# NovaSMTPracticeVX.net
KiCad netlist of a schematic drawn in EAGLE
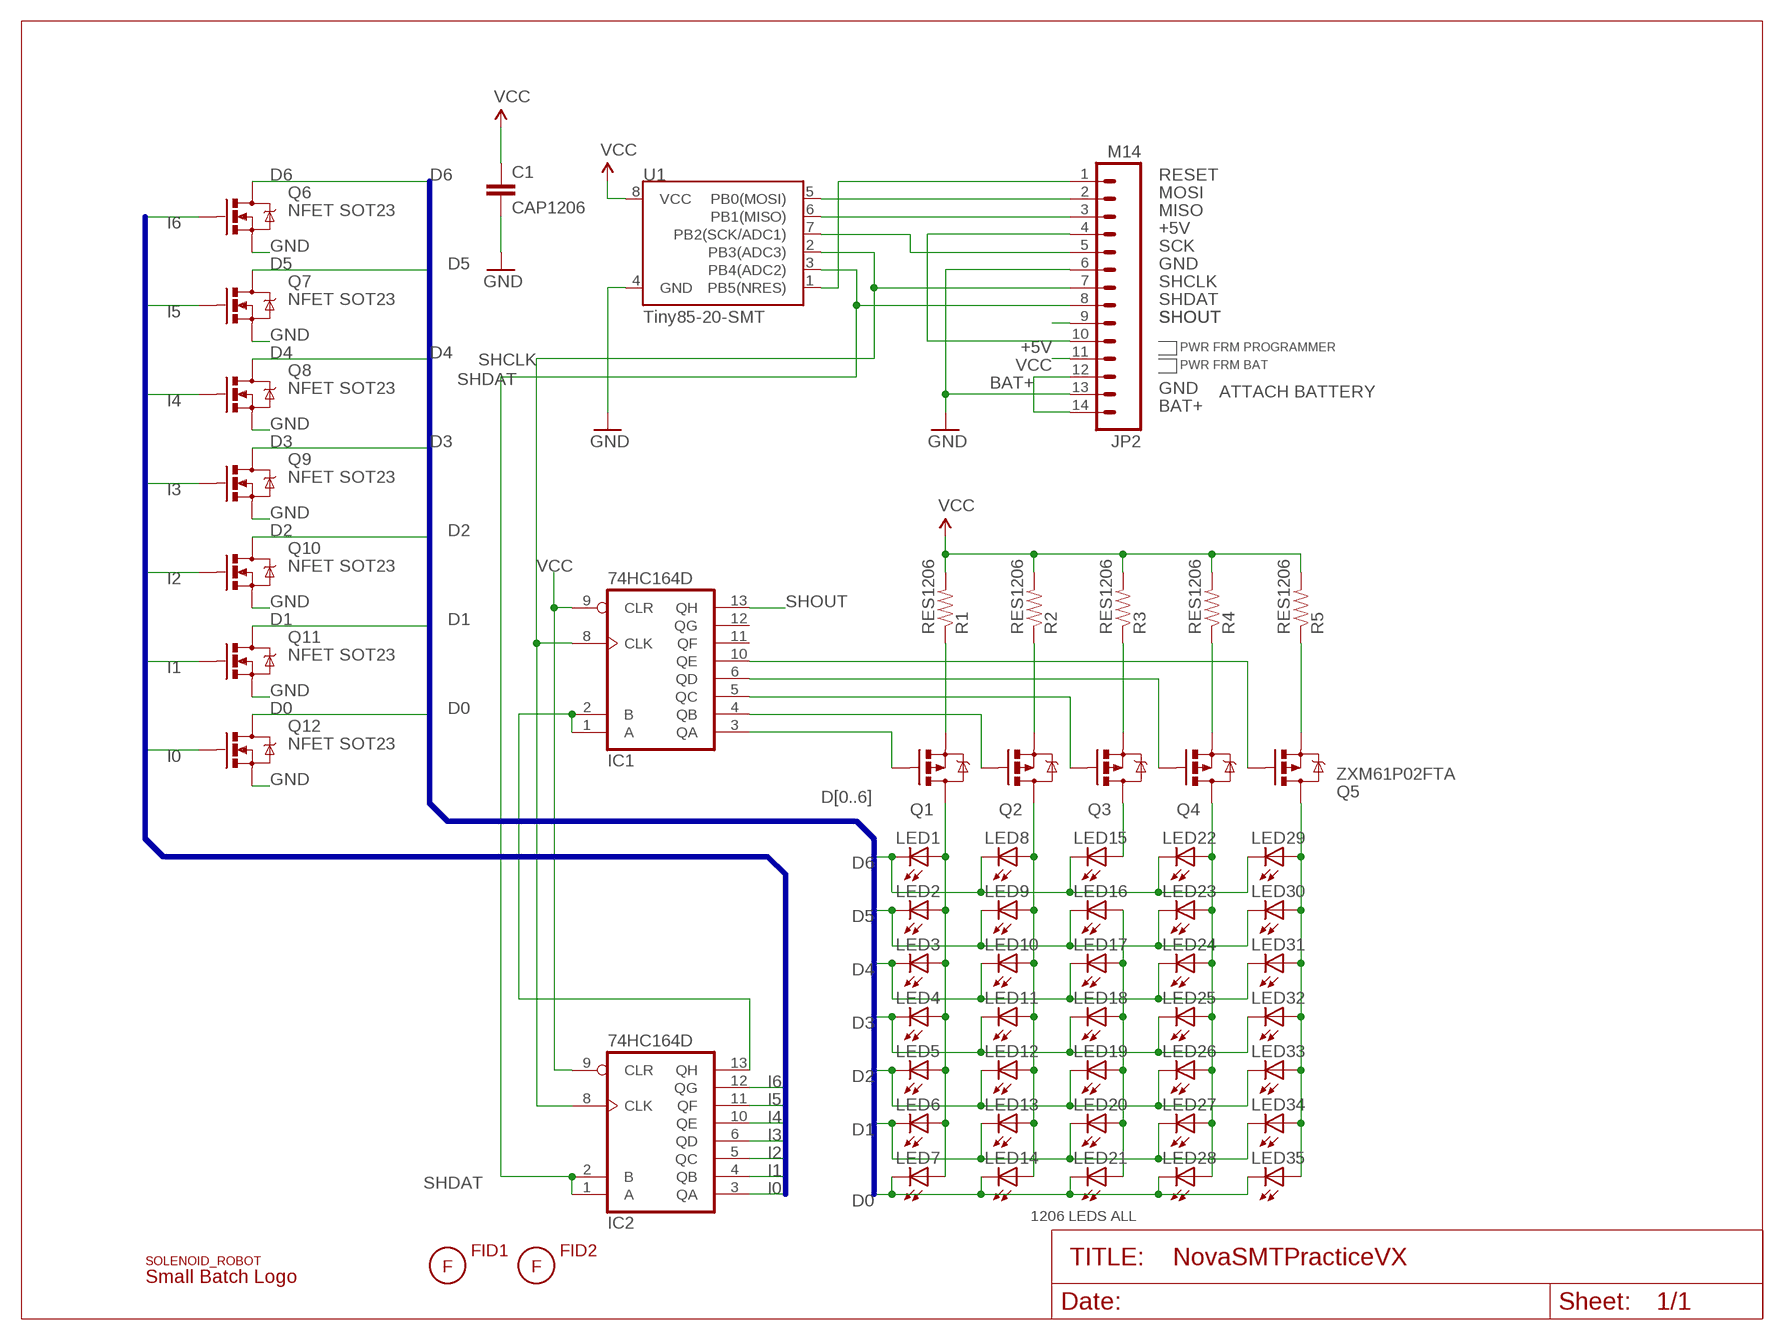
[diagram p0: schematic, sheet 1]

(export (version "E")
  (design (tool "Eeschema 10.0.6"))
  (components
    (comp (ref "C1")
      (value "CAP1206")
      (footprint "eagle-import:1206")
      (libsource (lib "eagle-import") (part "CAP1206"))
    )
    (comp (ref "FID1")
      (value "FIDUCIAL")
      (footprint "eagle-import:FID05MM")
      (libsource (lib "eagle-import") (part "FIDUCIAL"))
    )
    (comp (ref "FID2")
      (value "FIDUCIAL")
      (footprint "eagle-import:FID05MM")
      (libsource (lib "eagle-import") (part "FIDUCIAL"))
    )
    (comp (ref "IC1")
      (value "74HC164D")
      (footprint "eagle-import:SO14")
      (libsource (lib "eagle-import") (part "74164DHC"))
    )
    (comp (ref "IC2")
      (value "74HC164D")
      (footprint "eagle-import:SO14")
      (libsource (lib "eagle-import") (part "74164DHC"))
    )
    (comp (ref "JP2")
      (value "M14")
      (footprint "eagle-import:1X14_SMTPADS")
      (libsource (lib "eagle-import") (part "M14"))
    )
    (comp (ref "LED1")
      (value "LED1206")
      (footprint "eagle-import:LED-1206")
      (libsource (lib "eagle-import") (part "LED1206"))
    )
    (comp (ref "LED2")
      (value "LED1206")
      (footprint "eagle-import:LED-1206")
      (libsource (lib "eagle-import") (part "LED1206"))
    )
    (comp (ref "LED3")
      (value "LED1206")
      (footprint "eagle-import:LED-1206")
      (libsource (lib "eagle-import") (part "LED1206"))
    )
    (comp (ref "LED4")
      (value "LED1206")
      (footprint "eagle-import:LED-1206")
      (libsource (lib "eagle-import") (part "LED1206"))
    )
    (comp (ref "LED5")
      (value "LED1206")
      (footprint "eagle-import:LED-1206")
      (libsource (lib "eagle-import") (part "LED1206"))
    )
    (comp (ref "LED6")
      (value "LED1206")
      (footprint "eagle-import:LED-1206")
      (libsource (lib "eagle-import") (part "LED1206"))
    )
    (comp (ref "LED7")
      (value "LED1206")
      (footprint "eagle-import:LED-1206")
      (libsource (lib "eagle-import") (part "LED1206"))
    )
    (comp (ref "LED8")
      (value "LED1206")
      (footprint "eagle-import:LED-1206")
      (libsource (lib "eagle-import") (part "LED1206"))
    )
    (comp (ref "LED9")
      (value "LED1206")
      (footprint "eagle-import:LED-1206")
      (libsource (lib "eagle-import") (part "LED1206"))
    )
    (comp (ref "LED10")
      (value "LED1206")
      (footprint "eagle-import:LED-1206")
      (libsource (lib "eagle-import") (part "LED1206"))
    )
    (comp (ref "LED11")
      (value "LED1206")
      (footprint "eagle-import:LED-1206")
      (libsource (lib "eagle-import") (part "LED1206"))
    )
    (comp (ref "LED12")
      (value "LED1206")
      (footprint "eagle-import:LED-1206")
      (libsource (lib "eagle-import") (part "LED1206"))
    )
    (comp (ref "LED13")
      (value "LED1206")
      (footprint "eagle-import:LED-1206")
      (libsource (lib "eagle-import") (part "LED1206"))
    )
    (comp (ref "LED14")
      (value "LED1206")
      (footprint "eagle-import:LED-1206")
      (libsource (lib "eagle-import") (part "LED1206"))
    )
    (comp (ref "LED15")
      (value "LED1206")
      (footprint "eagle-import:LED-1206")
      (libsource (lib "eagle-import") (part "LED1206"))
    )
    (comp (ref "LED16")
      (value "LED1206")
      (footprint "eagle-import:LED-1206")
      (libsource (lib "eagle-import") (part "LED1206"))
    )
    (comp (ref "LED17")
      (value "LED1206")
      (footprint "eagle-import:LED-1206")
      (libsource (lib "eagle-import") (part "LED1206"))
    )
    (comp (ref "LED18")
      (value "LED1206")
      (footprint "eagle-import:LED-1206")
      (libsource (lib "eagle-import") (part "LED1206"))
    )
    (comp (ref "LED19")
      (value "LED1206")
      (footprint "eagle-import:LED-1206")
      (libsource (lib "eagle-import") (part "LED1206"))
    )
    (comp (ref "LED20")
      (value "LED1206")
      (footprint "eagle-import:LED-1206")
      (libsource (lib "eagle-import") (part "LED1206"))
    )
    (comp (ref "LED21")
      (value "LED1206")
      (footprint "eagle-import:LED-1206")
      (libsource (lib "eagle-import") (part "LED1206"))
    )
    (comp (ref "LED22")
      (value "LED1206")
      (footprint "eagle-import:LED-1206")
      (libsource (lib "eagle-import") (part "LED1206"))
    )
    (comp (ref "LED23")
      (value "LED1206")
      (footprint "eagle-import:LED-1206")
      (libsource (lib "eagle-import") (part "LED1206"))
    )
    (comp (ref "LED24")
      (value "LED1206")
      (footprint "eagle-import:LED-1206")
      (libsource (lib "eagle-import") (part "LED1206"))
    )
    (comp (ref "LED25")
      (value "LED1206")
      (footprint "eagle-import:LED-1206")
      (libsource (lib "eagle-import") (part "LED1206"))
    )
    (comp (ref "LED26")
      (value "LED1206")
      (footprint "eagle-import:LED-1206")
      (libsource (lib "eagle-import") (part "LED1206"))
    )
    (comp (ref "LED27")
      (value "LED1206")
      (footprint "eagle-import:LED-1206")
      (libsource (lib "eagle-import") (part "LED1206"))
    )
    (comp (ref "LED28")
      (value "LED1206")
      (footprint "eagle-import:LED-1206")
      (libsource (lib "eagle-import") (part "LED1206"))
    )
    (comp (ref "LED29")
      (value "LED1206")
      (footprint "eagle-import:LED-1206")
      (libsource (lib "eagle-import") (part "LED1206"))
    )
    (comp (ref "LED30")
      (value "LED1206")
      (footprint "eagle-import:LED-1206")
      (libsource (lib "eagle-import") (part "LED1206"))
    )
    (comp (ref "LED31")
      (value "LED1206")
      (footprint "eagle-import:LED-1206")
      (libsource (lib "eagle-import") (part "LED1206"))
    )
    (comp (ref "LED32")
      (value "LED1206")
      (footprint "eagle-import:LED-1206")
      (libsource (lib "eagle-import") (part "LED1206"))
    )
    (comp (ref "LED33")
      (value "LED1206")
      (footprint "eagle-import:LED-1206")
      (libsource (lib "eagle-import") (part "LED1206"))
    )
    (comp (ref "LED34")
      (value "LED1206")
      (footprint "eagle-import:LED-1206")
      (libsource (lib "eagle-import") (part "LED1206"))
    )
    (comp (ref "LED35")
      (value "LED1206")
      (footprint "eagle-import:LED-1206")
      (libsource (lib "eagle-import") (part "LED1206"))
    )
    (comp (ref "Q1")
      (value "MOSFET-PCHANNELSMD")
      (footprint "eagle-import:SOT23-3")
      (libsource (lib "eagle-import") (part "MOSFET-PCHANNELSMD"))
    )
    (comp (ref "Q2")
      (value "MOSFET-PCHANNELSMD")
      (footprint "eagle-import:SOT23-3")
      (libsource (lib "eagle-import") (part "MOSFET-PCHANNELSMD"))
    )
    (comp (ref "Q3")
      (value "MOSFET-PCHANNELSMD")
      (footprint "eagle-import:SOT23-3")
      (libsource (lib "eagle-import") (part "MOSFET-PCHANNELSMD"))
    )
    (comp (ref "Q4")
      (value "MOSFET-PCHANNELSMD")
      (footprint "eagle-import:SOT23-3")
      (libsource (lib "eagle-import") (part "MOSFET-PCHANNELSMD"))
    )
    (comp (ref "Q5")
      (value "ZXM61P02FTA")
      (footprint "eagle-import:SOT23-3")
      (libsource (lib "eagle-import") (part "MOSFET-PCHANNELSMD"))
    )
    (comp (ref "Q6")
      (value "NFET SOT23")
      (footprint "eagle-import:SOT23-3")
      (libsource (lib "eagle-import") (part "MOSFET-NCHANNELSMD"))
    )
    (comp (ref "Q7")
      (value "NFET SOT23")
      (footprint "eagle-import:SOT23-3")
      (libsource (lib "eagle-import") (part "MOSFET-NCHANNELSMD"))
    )
    (comp (ref "Q8")
      (value "NFET SOT23")
      (footprint "eagle-import:SOT23-3")
      (libsource (lib "eagle-import") (part "MOSFET-NCHANNELSMD"))
    )
    (comp (ref "Q9")
      (value "NFET SOT23")
      (footprint "eagle-import:SOT23-3")
      (libsource (lib "eagle-import") (part "MOSFET-NCHANNELSMD"))
    )
    (comp (ref "Q10")
      (value "NFET SOT23")
      (footprint "eagle-import:SOT23-3")
      (libsource (lib "eagle-import") (part "MOSFET-NCHANNELSMD"))
    )
    (comp (ref "Q11")
      (value "NFET SOT23")
      (footprint "eagle-import:SOT23-3")
      (libsource (lib "eagle-import") (part "MOSFET-NCHANNELSMD"))
    )
    (comp (ref "Q12")
      (value "NFET SOT23")
      (footprint "eagle-import:SOT23-3")
      (libsource (lib "eagle-import") (part "MOSFET-NCHANNELSMD"))
    )
    (comp (ref "R1")
      (value "RES1206")
      (footprint "eagle-import:1206")
      (libsource (lib "eagle-import") (part "RES1206"))
    )
    (comp (ref "R2")
      (value "RES1206")
      (footprint "eagle-import:1206")
      (libsource (lib "eagle-import") (part "RES1206"))
    )
    (comp (ref "R3")
      (value "RES1206")
      (footprint "eagle-import:1206")
      (libsource (lib "eagle-import") (part "RES1206"))
    )
    (comp (ref "R4")
      (value "RES1206")
      (footprint "eagle-import:1206")
      (libsource (lib "eagle-import") (part "RES1206"))
    )
    (comp (ref "R5")
      (value "RES1206")
      (footprint "eagle-import:1206")
      (libsource (lib "eagle-import") (part "RES1206"))
    )
    (comp (ref "U$1")
      (value "SOLENOID_ROBOT")
      (footprint "eagle-import:SOLENOID_ROBT_450MIL")
      (libsource (lib "eagle-import") (part "SOLENOID_ROBOT"))
    )
    (comp (ref "U$4")
      (value "SMALLBATCH_LOGO750W")
      (footprint "eagle-import:SMALLBATCH_750W")
      (libsource (lib "eagle-import") (part "SMALLBATCH_LOGO750W"))
    )
    (comp (ref "U1")
      (value "Tiny85-20-SMT")
      (footprint "eagle-import:SO08-EIAJ")
      (libsource (lib "eagle-import") (part "ATTINY45TINY85-20-SMT"))
    )
  )
  (nets
    (net (code "1") (name "/+5V") (class "Default")
      (node (ref "JP2") (pin "10") (pinfunction "10_10") (pintype "passive"))
      (node (ref "JP2") (pin "4") (pinfunction "4_4") (pintype "passive"))
    )
    (net (code "2") (name "/BAT+") (class "Default")
      (node (ref "JP2") (pin "12") (pinfunction "12_12") (pintype "passive"))
      (node (ref "JP2") (pin "14") (pinfunction "14_14") (pintype "passive"))
    )
    (net (code "3") (name "/D0") (class "Default")
      (node (ref "LED14") (pin "C") (pinfunction "C_C") (pintype "passive"))
      (node (ref "LED21") (pin "C") (pinfunction "C_C") (pintype "passive"))
      (node (ref "LED28") (pin "C") (pinfunction "C_C") (pintype "passive"))
      (node (ref "LED35") (pin "C") (pinfunction "C_C") (pintype "passive"))
      (node (ref "LED7") (pin "C") (pinfunction "C_C") (pintype "passive"))
      (node (ref "Q12") (pin "3") (pinfunction "D_3") (pintype "passive"))
    )
    (net (code "4") (name "/D1") (class "Default")
      (node (ref "LED13") (pin "C") (pinfunction "C_C") (pintype "passive"))
      (node (ref "LED20") (pin "C") (pinfunction "C_C") (pintype "passive"))
      (node (ref "LED27") (pin "C") (pinfunction "C_C") (pintype "passive"))
      (node (ref "LED34") (pin "C") (pinfunction "C_C") (pintype "passive"))
      (node (ref "LED6") (pin "C") (pinfunction "C_C") (pintype "passive"))
      (node (ref "Q11") (pin "3") (pinfunction "D_3") (pintype "passive"))
    )
    (net (code "5") (name "/D2") (class "Default")
      (node (ref "LED12") (pin "C") (pinfunction "C_C") (pintype "passive"))
      (node (ref "LED19") (pin "C") (pinfunction "C_C") (pintype "passive"))
      (node (ref "LED26") (pin "C") (pinfunction "C_C") (pintype "passive"))
      (node (ref "LED33") (pin "C") (pinfunction "C_C") (pintype "passive"))
      (node (ref "LED5") (pin "C") (pinfunction "C_C") (pintype "passive"))
      (node (ref "Q10") (pin "3") (pinfunction "D_3") (pintype "passive"))
    )
    (net (code "6") (name "/D3") (class "Default")
      (node (ref "LED11") (pin "C") (pinfunction "C_C") (pintype "passive"))
      (node (ref "LED18") (pin "C") (pinfunction "C_C") (pintype "passive"))
      (node (ref "LED25") (pin "C") (pinfunction "C_C") (pintype "passive"))
      (node (ref "LED32") (pin "C") (pinfunction "C_C") (pintype "passive"))
      (node (ref "LED4") (pin "C") (pinfunction "C_C") (pintype "passive"))
      (node (ref "Q9") (pin "3") (pinfunction "D_3") (pintype "passive"))
    )
    (net (code "7") (name "/D4") (class "Default")
      (node (ref "LED10") (pin "C") (pinfunction "C_C") (pintype "passive"))
      (node (ref "LED17") (pin "C") (pinfunction "C_C") (pintype "passive"))
      (node (ref "LED24") (pin "C") (pinfunction "C_C") (pintype "passive"))
      (node (ref "LED3") (pin "C") (pinfunction "C_C") (pintype "passive"))
      (node (ref "LED31") (pin "C") (pinfunction "C_C") (pintype "passive"))
      (node (ref "Q8") (pin "3") (pinfunction "D_3") (pintype "passive"))
    )
    (net (code "8") (name "/D5") (class "Default")
      (node (ref "LED16") (pin "C") (pinfunction "C_C") (pintype "passive"))
      (node (ref "LED2") (pin "C") (pinfunction "C_C") (pintype "passive"))
      (node (ref "LED23") (pin "C") (pinfunction "C_C") (pintype "passive"))
      (node (ref "LED30") (pin "C") (pinfunction "C_C") (pintype "passive"))
      (node (ref "LED9") (pin "C") (pinfunction "C_C") (pintype "passive"))
      (node (ref "Q7") (pin "3") (pinfunction "D_3") (pintype "passive"))
    )
    (net (code "9") (name "/D6") (class "Default")
      (node (ref "LED1") (pin "C") (pinfunction "C_C") (pintype "passive"))
      (node (ref "LED15") (pin "C") (pinfunction "C_C") (pintype "passive"))
      (node (ref "LED22") (pin "C") (pinfunction "C_C") (pintype "passive"))
      (node (ref "LED29") (pin "C") (pinfunction "C_C") (pintype "passive"))
      (node (ref "LED8") (pin "C") (pinfunction "C_C") (pintype "passive"))
      (node (ref "Q6") (pin "3") (pinfunction "D_3") (pintype "passive"))
    )
    (net (code "10") (name "/I0") (class "Default")
      (node (ref "IC2") (pin "3") (pinfunction "QA_3") (pintype "output"))
      (node (ref "Q12") (pin "1") (pinfunction "G_1") (pintype "passive"))
    )
    (net (code "11") (name "/I1") (class "Default")
      (node (ref "IC2") (pin "4") (pinfunction "QB_4") (pintype "output"))
      (node (ref "Q11") (pin "1") (pinfunction "G_1") (pintype "passive"))
    )
    (net (code "12") (name "/I2") (class "Default")
      (node (ref "IC2") (pin "5") (pinfunction "QC_5") (pintype "output"))
      (node (ref "Q10") (pin "1") (pinfunction "G_1") (pintype "passive"))
    )
    (net (code "13") (name "/I3") (class "Default")
      (node (ref "IC2") (pin "6") (pinfunction "QD_6") (pintype "output"))
      (node (ref "Q9") (pin "1") (pinfunction "G_1") (pintype "passive"))
    )
    (net (code "14") (name "/I4") (class "Default")
      (node (ref "IC2") (pin "10") (pinfunction "QE_10") (pintype "output"))
      (node (ref "Q8") (pin "1") (pinfunction "G_1") (pintype "passive"))
    )
    (net (code "15") (name "/I5") (class "Default")
      (node (ref "IC2") (pin "11") (pinfunction "QF_11") (pintype "output"))
      (node (ref "Q7") (pin "1") (pinfunction "G_1") (pintype "passive"))
    )
    (net (code "16") (name "/I6") (class "Default")
      (node (ref "IC2") (pin "12") (pinfunction "QG_12") (pintype "output"))
      (node (ref "Q6") (pin "1") (pinfunction "G_1") (pintype "passive"))
    )
    (net (code "17") (name "/MISO") (class "Default")
      (node (ref "JP2") (pin "3") (pinfunction "3_3") (pintype "passive"))
      (node (ref "U1") (pin "6") (pinfunction "PB1(MISO)_6") (pintype "bidirectional"))
    )
    (net (code "18") (name "/MOSI") (class "Default")
      (node (ref "JP2") (pin "2") (pinfunction "2_2") (pintype "passive"))
      (node (ref "U1") (pin "5") (pinfunction "PB0(MOSI)_5") (pintype "bidirectional"))
    )
    (net (code "19") (name "/RESET") (class "Default")
      (node (ref "JP2") (pin "1") (pinfunction "1_1") (pintype "passive"))
      (node (ref "U1") (pin "1") (pinfunction "PB5(NRES)_1") (pintype "bidirectional"))
    )
    (net (code "20") (name "/SCK") (class "Default")
      (node (ref "JP2") (pin "5") (pinfunction "5_5") (pintype "passive"))
      (node (ref "U1") (pin "7") (pinfunction "PB2(SCK/ADC1)_7") (pintype "bidirectional"))
    )
    (net (code "21") (name "/SHCLK") (class "Default")
      (node (ref "IC1") (pin "8") (pinfunction "CLK_8") (pintype "input"))
      (node (ref "IC2") (pin "8") (pinfunction "CLK_8") (pintype "input"))
      (node (ref "JP2") (pin "7") (pinfunction "7_7") (pintype "passive"))
      (node (ref "U1") (pin "2") (pinfunction "PB3(ADC3)_2") (pintype "bidirectional"))
    )
    (net (code "22") (name "/SHDAT") (class "Default")
      (node (ref "IC2") (pin "1") (pinfunction "A_1") (pintype "input"))
      (node (ref "IC2") (pin "2") (pinfunction "B_2") (pintype "input"))
      (node (ref "JP2") (pin "8") (pinfunction "8_8") (pintype "passive"))
      (node (ref "U1") (pin "3") (pinfunction "PB4(ADC2)_3") (pintype "bidirectional"))
    )
    (net (code "23") (name "/SHOUT") (class "Default")
      (node (ref "IC1") (pin "13") (pinfunction "QH_13") (pintype "output"))
      (node (ref "JP2") (pin "9") (pinfunction "9_9") (pintype "passive"))
    )
    (net (code "24") (name "GND") (class "Default")
      (node (ref "C1") (pin "2") (pinfunction "2_2") (pintype "passive"))
      (node (ref "JP2") (pin "13") (pinfunction "13_13") (pintype "passive"))
      (node (ref "JP2") (pin "6") (pinfunction "6_6") (pintype "passive"))
      (node (ref "Q10") (pin "2") (pinfunction "S_2") (pintype "passive"))
      (node (ref "Q11") (pin "2") (pinfunction "S_2") (pintype "passive"))
      (node (ref "Q12") (pin "2") (pinfunction "S_2") (pintype "passive"))
      (node (ref "Q6") (pin "2") (pinfunction "S_2") (pintype "passive"))
      (node (ref "Q7") (pin "2") (pinfunction "S_2") (pintype "passive"))
      (node (ref "Q8") (pin "2") (pinfunction "S_2") (pintype "passive"))
      (node (ref "Q9") (pin "2") (pinfunction "S_2") (pintype "passive"))
      (node (ref "U1") (pin "4") (pinfunction "GND_4") (pintype "bidirectional"))
    )
    (net (code "25") (name "Net-(IC1A-A)") (class "Default")
      (node (ref "IC1") (pin "1") (pinfunction "A_1") (pintype "input"))
      (node (ref "IC1") (pin "2") (pinfunction "B_2") (pintype "input"))
      (node (ref "IC2") (pin "13") (pinfunction "QH_13") (pintype "output"))
    )
    (net (code "26") (name "Net-(IC1A-QA)") (class "Default")
      (node (ref "IC1") (pin "3") (pinfunction "QA_3") (pintype "output"))
      (node (ref "Q1") (pin "1") (pinfunction "G_1") (pintype "passive"))
    )
    (net (code "27") (name "Net-(IC1A-QB)") (class "Default")
      (node (ref "IC1") (pin "4") (pinfunction "QB_4") (pintype "output"))
      (node (ref "Q2") (pin "1") (pinfunction "G_1") (pintype "passive"))
    )
    (net (code "28") (name "Net-(IC1A-QC)") (class "Default")
      (node (ref "IC1") (pin "5") (pinfunction "QC_5") (pintype "output"))
      (node (ref "Q3") (pin "1") (pinfunction "G_1") (pintype "passive"))
    )
    (net (code "29") (name "Net-(IC1A-QD)") (class "Default")
      (node (ref "IC1") (pin "6") (pinfunction "QD_6") (pintype "output"))
      (node (ref "Q4") (pin "1") (pinfunction "G_1") (pintype "passive"))
    )
    (net (code "30") (name "Net-(IC1A-QE)") (class "Default")
      (node (ref "IC1") (pin "10") (pinfunction "QE_10") (pintype "output"))
      (node (ref "Q5") (pin "1") (pinfunction "G_1") (pintype "passive"))
    )
    (net (code "31") (name "Net-(LED16-PadA)") (class "Default")
      (node (ref "LED16") (pin "A") (pinfunction "A_A") (pintype "passive"))
      (node (ref "LED17") (pin "A") (pinfunction "A_A") (pintype "passive"))
      (node (ref "LED18") (pin "A") (pinfunction "A_A") (pintype "passive"))
      (node (ref "LED19") (pin "A") (pinfunction "A_A") (pintype "passive"))
      (node (ref "LED20") (pin "A") (pinfunction "A_A") (pintype "passive"))
      (node (ref "LED21") (pin "A") (pinfunction "A_A") (pintype "passive"))
    )
    (net (code "32") (name "Net-(Q1-D)") (class "Default")
      (node (ref "LED1") (pin "A") (pinfunction "A_A") (pintype "passive"))
      (node (ref "LED2") (pin "A") (pinfunction "A_A") (pintype "passive"))
      (node (ref "LED3") (pin "A") (pinfunction "A_A") (pintype "passive"))
      (node (ref "LED4") (pin "A") (pinfunction "A_A") (pintype "passive"))
      (node (ref "LED5") (pin "A") (pinfunction "A_A") (pintype "passive"))
      (node (ref "LED6") (pin "A") (pinfunction "A_A") (pintype "passive"))
      (node (ref "LED7") (pin "A") (pinfunction "A_A") (pintype "passive"))
      (node (ref "Q1") (pin "3") (pinfunction "D_3") (pintype "passive"))
    )
    (net (code "33") (name "Net-(Q1-S)") (class "Default")
      (node (ref "Q1") (pin "2") (pinfunction "S_2") (pintype "passive"))
      (node (ref "R1") (pin "1") (pinfunction "1_1") (pintype "passive"))
    )
    (net (code "34") (name "Net-(Q2-D)") (class "Default")
      (node (ref "LED10") (pin "A") (pinfunction "A_A") (pintype "passive"))
      (node (ref "LED11") (pin "A") (pinfunction "A_A") (pintype "passive"))
      (node (ref "LED12") (pin "A") (pinfunction "A_A") (pintype "passive"))
      (node (ref "LED13") (pin "A") (pinfunction "A_A") (pintype "passive"))
      (node (ref "LED14") (pin "A") (pinfunction "A_A") (pintype "passive"))
      (node (ref "LED8") (pin "A") (pinfunction "A_A") (pintype "passive"))
      (node (ref "LED9") (pin "A") (pinfunction "A_A") (pintype "passive"))
      (node (ref "Q2") (pin "3") (pinfunction "D_3") (pintype "passive"))
    )
    (net (code "35") (name "Net-(Q2-S)") (class "Default")
      (node (ref "Q2") (pin "2") (pinfunction "S_2") (pintype "passive"))
      (node (ref "R2") (pin "1") (pinfunction "1_1") (pintype "passive"))
    )
    (net (code "36") (name "Net-(Q3-D)") (class "Default")
      (node (ref "LED15") (pin "A") (pinfunction "A_A") (pintype "passive"))
      (node (ref "Q3") (pin "3") (pinfunction "D_3") (pintype "passive"))
    )
    (net (code "37") (name "Net-(Q3-S)") (class "Default")
      (node (ref "Q3") (pin "2") (pinfunction "S_2") (pintype "passive"))
      (node (ref "R3") (pin "1") (pinfunction "1_1") (pintype "passive"))
    )
    (net (code "38") (name "Net-(Q4-D)") (class "Default")
      (node (ref "LED22") (pin "A") (pinfunction "A_A") (pintype "passive"))
      (node (ref "LED23") (pin "A") (pinfunction "A_A") (pintype "passive"))
      (node (ref "LED24") (pin "A") (pinfunction "A_A") (pintype "passive"))
      (node (ref "LED25") (pin "A") (pinfunction "A_A") (pintype "passive"))
      (node (ref "LED26") (pin "A") (pinfunction "A_A") (pintype "passive"))
      (node (ref "LED27") (pin "A") (pinfunction "A_A") (pintype "passive"))
      (node (ref "LED28") (pin "A") (pinfunction "A_A") (pintype "passive"))
      (node (ref "Q4") (pin "3") (pinfunction "D_3") (pintype "passive"))
    )
    (net (code "39") (name "Net-(Q4-S)") (class "Default")
      (node (ref "Q4") (pin "2") (pinfunction "S_2") (pintype "passive"))
      (node (ref "R4") (pin "1") (pinfunction "1_1") (pintype "passive"))
    )
    (net (code "40") (name "Net-(Q5-D)") (class "Default")
      (node (ref "LED29") (pin "A") (pinfunction "A_A") (pintype "passive"))
      (node (ref "LED30") (pin "A") (pinfunction "A_A") (pintype "passive"))
      (node (ref "LED31") (pin "A") (pinfunction "A_A") (pintype "passive"))
      (node (ref "LED32") (pin "A") (pinfunction "A_A") (pintype "passive"))
      (node (ref "LED33") (pin "A") (pinfunction "A_A") (pintype "passive"))
      (node (ref "LED34") (pin "A") (pinfunction "A_A") (pintype "passive"))
      (node (ref "LED35") (pin "A") (pinfunction "A_A") (pintype "passive"))
      (node (ref "Q5") (pin "3") (pinfunction "D_3") (pintype "passive"))
    )
    (net (code "41") (name "Net-(Q5-S)") (class "Default")
      (node (ref "Q5") (pin "2") (pinfunction "S_2") (pintype "passive"))
      (node (ref "R5") (pin "1") (pinfunction "1_1") (pintype "passive"))
    )
    (net (code "42") (name "VCC") (class "Default")
      (node (ref "C1") (pin "1") (pinfunction "1_1") (pintype "passive"))
      (node (ref "IC1") (pin "9") (pinfunction "CLR_9") (pintype "input"))
      (node (ref "IC2") (pin "9") (pinfunction "CLR_9") (pintype "input"))
      (node (ref "JP2") (pin "11") (pinfunction "11_11") (pintype "passive"))
      (node (ref "R1") (pin "2") (pinfunction "2_2") (pintype "passive"))
      (node (ref "R2") (pin "2") (pinfunction "2_2") (pintype "passive"))
      (node (ref "R3") (pin "2") (pinfunction "2_2") (pintype "passive"))
      (node (ref "R4") (pin "2") (pinfunction "2_2") (pintype "passive"))
      (node (ref "R5") (pin "2") (pinfunction "2_2") (pintype "passive"))
      (node (ref "U1") (pin "8") (pinfunction "VCC_8") (pintype "bidirectional"))
    )
    (net (code "43") (name "unconnected-(IC1A-QF-Pad11)") (class "Default")
      (node (ref "IC1") (pin "11") (pinfunction "QF_11") (pintype "output"))
    )
    (net (code "44") (name "unconnected-(IC1A-QG-Pad12)") (class "Default")
      (node (ref "IC1") (pin "12") (pinfunction "QG_12") (pintype "output"))
    )
  )
)
